# ctr_brd.net
KiCad netlist of a schematic drawn in EAGLE
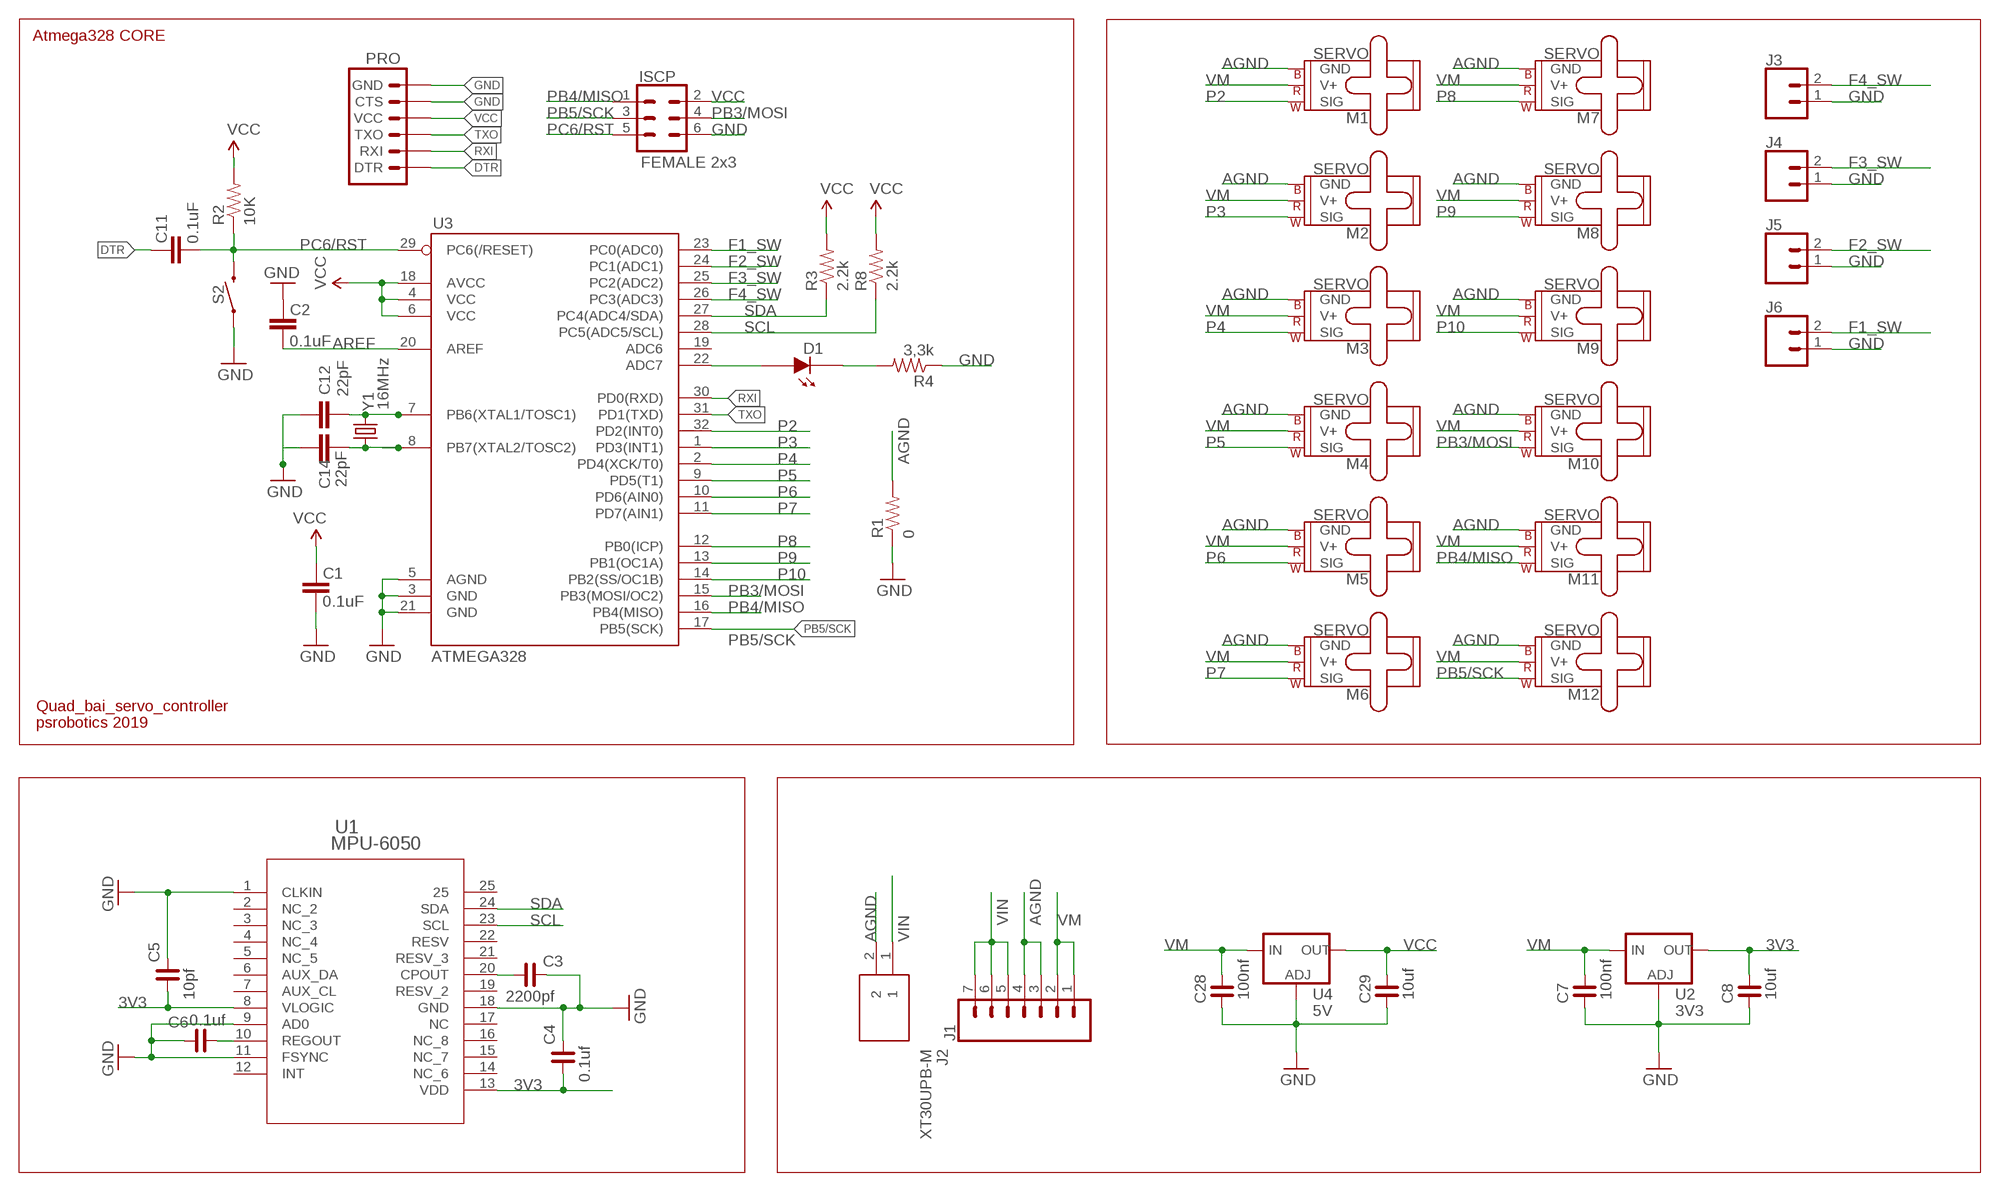
[diagram p0: schematic, sheet 1]

(export (version "E")
  (design (tool "Eeschema 10.0.6"))
  (components
    (comp (ref "C1")
      (value "0.1uF")
      (footprint "eagle-import:0603-CAP")
      (libsource (lib "eagle-import") (part "CAP0603-CAP"))
    )
    (comp (ref "C2")
      (value "0.1uF")
      (footprint "eagle-import:0603-CAP")
      (libsource (lib "eagle-import") (part "CAP0603-CAP"))
    )
    (comp (ref "C3")
      (value "2200pf")
      (footprint "eagle-import:C0603")
      (libsource (lib "eagle-import") (part "C_0603"))
    )
    (comp (ref "C4")
      (value "0.1uf")
      (footprint "eagle-import:C0603")
      (libsource (lib "eagle-import") (part "C_0603"))
    )
    (comp (ref "C5")
      (value "10pf")
      (footprint "eagle-import:C0603")
      (libsource (lib "eagle-import") (part "C_0603"))
    )
    (comp (ref "C6")
      (value "0.1uf")
      (footprint "eagle-import:C0603")
      (libsource (lib "eagle-import") (part "C_0603"))
    )
    (comp (ref "C7")
      (value "100nf")
      (footprint "eagle-import:C0603")
      (libsource (lib "eagle-import") (part "C_0603"))
    )
    (comp (ref "C8")
      (value "10uf")
      (footprint "eagle-import:C0603")
      (libsource (lib "eagle-import") (part "C_0603"))
    )
    (comp (ref "C11")
      (value "0.1uF")
      (footprint "eagle-import:0603-CAP")
      (libsource (lib "eagle-import") (part "CAP0603-CAP"))
    )
    (comp (ref "C12")
      (value "22pF")
      (footprint "eagle-import:0603")
      (libsource (lib "eagle-import") (part "22PF-0603-50V-5%"))
    )
    (comp (ref "C14")
      (value "22pF")
      (footprint "eagle-import:0603")
      (libsource (lib "eagle-import") (part "22PF-0603-50V-5%"))
    )
    (comp (ref "C28")
      (value "100nf")
      (footprint "eagle-import:C0603")
      (libsource (lib "eagle-import") (part "C_0603"))
    )
    (comp (ref "C29")
      (value "10uf")
      (footprint "eagle-import:C0603")
      (libsource (lib "eagle-import") (part "C_0603"))
    )
    (comp (ref "D1")
      (value "LEDB")
      (footprint "eagle-import:0603P")
      (libsource (lib "eagle-import") (part "LEDB"))
    )
    (comp (ref "ISCP")
      (value "FEMALE 2x3")
      (footprint "eagle-import:2X3")
      (libsource (lib "eagle-import") (part "CONN_03X2FEMALE"))
    )
    (comp (ref "J1")
      (value "CONN_07LONGPADS")
      (footprint "eagle-import:1X07_LONGPADS")
      (libsource (lib "eagle-import") (part "CONN_07LONGPADS"))
    )
    (comp (ref "J2")
      (value "XT30UPB-M")
      (footprint "eagle-import:SHDR2W160P0X500_1X2_1020X520X1")
      (libsource (lib "eagle-import") (part "XT30UPB-M"))
    )
    (comp (ref "J3")
      (value "CONN_02LOCK")
      (footprint "eagle-import:1X02_LOCK")
      (libsource (lib "eagle-import") (part "CONN_02LOCK"))
    )
    (comp (ref "J4")
      (value "CONN_02LOCK")
      (footprint "eagle-import:1X02_LOCK")
      (libsource (lib "eagle-import") (part "CONN_02LOCK"))
    )
    (comp (ref "J5")
      (value "CONN_02LOCK")
      (footprint "eagle-import:1X02_LOCK")
      (libsource (lib "eagle-import") (part "CONN_02LOCK"))
    )
    (comp (ref "J6")
      (value "CONN_02LOCK")
      (footprint "eagle-import:1X02_LOCK")
      (libsource (lib "eagle-import") (part "CONN_02LOCK"))
    )
    (comp (ref "M1")
      (value "SERVO")
      (footprint "eagle-import:1X03")
      (libsource (lib "eagle-import") (part "SERVO"))
    )
    (comp (ref "M2")
      (value "SERVO")
      (footprint "eagle-import:1X03")
      (libsource (lib "eagle-import") (part "SERVO"))
    )
    (comp (ref "M3")
      (value "SERVO")
      (footprint "eagle-import:1X03")
      (libsource (lib "eagle-import") (part "SERVO"))
    )
    (comp (ref "M4")
      (value "SERVO")
      (footprint "eagle-import:1X03")
      (libsource (lib "eagle-import") (part "SERVO"))
    )
    (comp (ref "M5")
      (value "SERVO")
      (footprint "eagle-import:1X03")
      (libsource (lib "eagle-import") (part "SERVO"))
    )
    (comp (ref "M6")
      (value "SERVO")
      (footprint "eagle-import:1X03")
      (libsource (lib "eagle-import") (part "SERVO"))
    )
    (comp (ref "M7")
      (value "SERVO")
      (footprint "eagle-import:1X03")
      (libsource (lib "eagle-import") (part "SERVO"))
    )
    (comp (ref "M8")
      (value "SERVO")
      (footprint "eagle-import:1X03")
      (libsource (lib "eagle-import") (part "SERVO"))
    )
    (comp (ref "M9")
      (value "SERVO")
      (footprint "eagle-import:1X03")
      (libsource (lib "eagle-import") (part "SERVO"))
    )
    (comp (ref "M10")
      (value "SERVO")
      (footprint "eagle-import:1X03")
      (libsource (lib "eagle-import") (part "SERVO"))
    )
    (comp (ref "M11")
      (value "SERVO")
      (footprint "eagle-import:1X03")
      (libsource (lib "eagle-import") (part "SERVO"))
    )
    (comp (ref "M12")
      (value "SERVO")
      (footprint "eagle-import:1X03")
      (libsource (lib "eagle-import") (part "SERVO"))
    )
    (comp (ref "PRO")
      (value "FTDI Basic")
      (footprint "eagle-import:1X06")
      (libsource (lib "eagle-import") (part "ARDUINO_SERIAL_PROGRAMPTH"))
    )
    (comp (ref "R1")
      (value "0")
      (footprint "eagle-import:0603-RES")
      (libsource (lib "eagle-import") (part "RESISTOR0603-RES"))
    )
    (comp (ref "R2")
      (value "10K")
      (footprint "eagle-import:0603-RES")
      (libsource (lib "eagle-import") (part "RESISTOR0603-RES"))
    )
    (comp (ref "R3")
      (value "2.2k")
      (footprint "eagle-import:0603-RES")
      (libsource (lib "eagle-import") (part "RESISTOR0603-RES"))
    )
    (comp (ref "R4")
      (value "3,3k")
      (footprint "eagle-import:0603-RES")
      (libsource (lib "eagle-import") (part "RESISTOR0603-RES"))
    )
    (comp (ref "R8")
      (value "2.2k")
      (footprint "eagle-import:0603-RES")
      (libsource (lib "eagle-import") (part "RESISTOR0603-RES"))
    )
    (comp (ref "S2")
      (value "MOMENTARY-SWITCH-SPST-SMD-6.0X3.5MM")
      (footprint "eagle-import:TACTILE_SWITCH_SMD_6.0X3.5MM")
      (libsource (lib "eagle-import") (part "MOMENTARY-SWITCH-SPST-SMD-6.0X3.5MM"))
    )
    (comp (ref "U1")
      (value "MPU-6050")
      (footprint "eagle-import:QFN24_4X4X0P9_IVS")
      (fields (field (name "COPYRIGHT") "Copyright (C) 2018 Accelerated Designs. All rights reserved"))
      (libsource (lib "eagle-import") (part "MPU-6050"))
    )
    (comp (ref "U2")
      (value "3V3")
      (footprint "eagle-import:SOT223")
      (libsource (lib "eagle-import") (part "V_REG_LM1117SOT223"))
    )
    (comp (ref "U3")
      (value "ATMEGA328")
      (footprint "eagle-import:TQFP32-08")
      (libsource (lib "eagle-import") (part "ATMEGA168"))
    )
    (comp (ref "U4")
      (value "5V")
      (footprint "eagle-import:SOT223")
      (libsource (lib "eagle-import") (part "V_REG_LM1117SOT223"))
    )
    (comp (ref "Y1")
      (value "16MHz")
      (footprint "eagle-import:CRYSTAL-SMD-5X3.2-4PAD")
      (libsource (lib "eagle-import") (part "CRYSTAL-16MHZSMD-5X3.2"))
    )
  )
  (nets
    (net (code "1") (name "/3V3") (class "Default")
      (node (ref "C4") (pin "1") (pinfunction "1_1") (pintype "passive"))
      (node (ref "C5") (pin "1") (pinfunction "1_1") (pintype "passive"))
      (node (ref "C8") (pin "2") (pinfunction "2_2") (pintype "passive"))
      (node (ref "U1") (pin "13") (pinfunction "VDD_13") (pintype "power_in"))
      (node (ref "U1") (pin "8") (pinfunction "VLOGIC_8") (pintype "power_in"))
      (node (ref "U2") (pin "2") (pinfunction "OUT_2") (pintype "output"))
      (node (ref "U2") (pin "4") (pinfunction "OUT_4") (pintype "output"))
    )
    (net (code "2") (name "/AGND") (class "Default")
      (node (ref "J1") (pin "3") (pinfunction "3_3") (pintype "passive"))
      (node (ref "J1") (pin "4") (pinfunction "4_4") (pintype "passive"))
      (node (ref "J2") (pin "2") (pinfunction "2_2") (pintype "bidirectional"))
      (node (ref "M1") (pin "3") (pinfunction "GND_3") (pintype "bidirectional"))
      (node (ref "M10") (pin "3") (pinfunction "GND_3") (pintype "bidirectional"))
      (node (ref "M11") (pin "3") (pinfunction "GND_3") (pintype "bidirectional"))
      (node (ref "M12") (pin "3") (pinfunction "GND_3") (pintype "bidirectional"))
      (node (ref "M2") (pin "3") (pinfunction "GND_3") (pintype "bidirectional"))
      (node (ref "M3") (pin "3") (pinfunction "GND_3") (pintype "bidirectional"))
      (node (ref "M4") (pin "3") (pinfunction "GND_3") (pintype "bidirectional"))
      (node (ref "M5") (pin "3") (pinfunction "GND_3") (pintype "bidirectional"))
      (node (ref "M6") (pin "3") (pinfunction "GND_3") (pintype "bidirectional"))
      (node (ref "M7") (pin "3") (pinfunction "GND_3") (pintype "bidirectional"))
      (node (ref "M8") (pin "3") (pinfunction "GND_3") (pintype "bidirectional"))
      (node (ref "M9") (pin "3") (pinfunction "GND_3") (pintype "bidirectional"))
      (node (ref "R1") (pin "2") (pinfunction "2_2") (pintype "passive"))
    )
    (net (code "3") (name "/AREF") (class "Default")
      (node (ref "C2") (pin "1") (pinfunction "1_1") (pintype "passive"))
      (node (ref "U3") (pin "20") (pinfunction "AREF_20") (pintype "bidirectional"))
    )
    (net (code "4") (name "/F1_SW") (class "Default")
      (node (ref "J6") (pin "2") (pinfunction "2_2") (pintype "passive"))
      (node (ref "U3") (pin "23") (pinfunction "PC0(ADC0)_23") (pintype "bidirectional"))
    )
    (net (code "5") (name "/F2_SW") (class "Default")
      (node (ref "J5") (pin "2") (pinfunction "2_2") (pintype "passive"))
      (node (ref "U3") (pin "24") (pinfunction "PC1(ADC1)_24") (pintype "bidirectional"))
    )
    (net (code "6") (name "/F3_SW") (class "Default")
      (node (ref "J4") (pin "2") (pinfunction "2_2") (pintype "passive"))
      (node (ref "U3") (pin "25") (pinfunction "PC2(ADC2)_25") (pintype "bidirectional"))
    )
    (net (code "7") (name "/F4_SW") (class "Default")
      (node (ref "J3") (pin "2") (pinfunction "2_2") (pintype "passive"))
      (node (ref "U3") (pin "26") (pinfunction "PC3(ADC3)_26") (pintype "bidirectional"))
    )
    (net (code "8") (name "/P2") (class "Default")
      (node (ref "M1") (pin "1") (pinfunction "SIG_1") (pintype "bidirectional"))
      (node (ref "U3") (pin "32") (pinfunction "PD2(INT0)_32") (pintype "bidirectional"))
    )
    (net (code "9") (name "/P3") (class "Default")
      (node (ref "M2") (pin "1") (pinfunction "SIG_1") (pintype "bidirectional"))
      (node (ref "U3") (pin "1") (pinfunction "PD3(INT1)_1") (pintype "bidirectional"))
    )
    (net (code "10") (name "/P4") (class "Default")
      (node (ref "M3") (pin "1") (pinfunction "SIG_1") (pintype "bidirectional"))
      (node (ref "U3") (pin "2") (pinfunction "PD4(XCK/T0)_2") (pintype "bidirectional"))
    )
    (net (code "11") (name "/P5") (class "Default")
      (node (ref "M4") (pin "1") (pinfunction "SIG_1") (pintype "bidirectional"))
      (node (ref "U3") (pin "9") (pinfunction "PD5(T1)_9") (pintype "bidirectional"))
    )
    (net (code "12") (name "/P6") (class "Default")
      (node (ref "M5") (pin "1") (pinfunction "SIG_1") (pintype "bidirectional"))
      (node (ref "U3") (pin "10") (pinfunction "PD6(AIN0)_10") (pintype "bidirectional"))
    )
    (net (code "13") (name "/P7") (class "Default")
      (node (ref "M6") (pin "1") (pinfunction "SIG_1") (pintype "bidirectional"))
      (node (ref "U3") (pin "11") (pinfunction "PD7(AIN1)_11") (pintype "bidirectional"))
    )
    (net (code "14") (name "/P8") (class "Default")
      (node (ref "M7") (pin "1") (pinfunction "SIG_1") (pintype "bidirectional"))
      (node (ref "U3") (pin "12") (pinfunction "PB0(ICP)_12") (pintype "bidirectional"))
    )
    (net (code "15") (name "/P9") (class "Default")
      (node (ref "M8") (pin "1") (pinfunction "SIG_1") (pintype "bidirectional"))
      (node (ref "U3") (pin "13") (pinfunction "PB1(OC1A)_13") (pintype "bidirectional"))
    )
    (net (code "16") (name "/P10") (class "Default")
      (node (ref "M9") (pin "1") (pinfunction "SIG_1") (pintype "bidirectional"))
      (node (ref "U3") (pin "14") (pinfunction "PB2(SS/OC1B)_14") (pintype "bidirectional"))
    )
    (net (code "17") (name "/PB3{slash}MOSI") (class "Default")
      (node (ref "ISCP") (pin "4") (pinfunction "4_4") (pintype "bidirectional"))
      (node (ref "M10") (pin "1") (pinfunction "SIG_1") (pintype "bidirectional"))
      (node (ref "U3") (pin "15") (pinfunction "PB3(MOSI/OC2)_15") (pintype "bidirectional"))
    )
    (net (code "18") (name "/PB4{slash}MISO") (class "Default")
      (node (ref "ISCP") (pin "1") (pinfunction "1_1") (pintype "bidirectional"))
      (node (ref "M11") (pin "1") (pinfunction "SIG_1") (pintype "bidirectional"))
      (node (ref "U3") (pin "16") (pinfunction "PB4(MISO)_16") (pintype "bidirectional"))
    )
    (net (code "19") (name "/PC6{slash}RST") (class "Default")
      (node (ref "C11") (pin "1") (pinfunction "1_1") (pintype "passive"))
      (node (ref "ISCP") (pin "5") (pinfunction "5_5") (pintype "bidirectional"))
      (node (ref "R2") (pin "1") (pinfunction "1_1") (pintype "passive"))
      (node (ref "S2") (pin "2") (pinfunction "2_2") (pintype "passive"))
      (node (ref "U3") (pin "29") (pinfunction "PC6(/RESET)_29") (pintype "bidirectional"))
    )
    (net (code "20") (name "/SCL") (class "Default")
      (node (ref "R8") (pin "1") (pinfunction "1_1") (pintype "passive"))
      (node (ref "U1") (pin "23") (pinfunction "SCL_23") (pintype "passive"))
      (node (ref "U3") (pin "28") (pinfunction "PC5(ADC5/SCL)_28") (pintype "bidirectional"))
    )
    (net (code "21") (name "/SDA") (class "Default")
      (node (ref "R3") (pin "1") (pinfunction "1_1") (pintype "passive"))
      (node (ref "U1") (pin "24") (pinfunction "SDA_24") (pintype "passive"))
      (node (ref "U3") (pin "27") (pinfunction "PC4(ADC4/SDA)_27") (pintype "bidirectional"))
    )
    (net (code "22") (name "/VIN") (class "Default")
      (node (ref "J1") (pin "5") (pinfunction "5_5") (pintype "passive"))
      (node (ref "J1") (pin "6") (pinfunction "6_6") (pintype "passive"))
      (node (ref "J1") (pin "7") (pinfunction "7_7") (pintype "passive"))
      (node (ref "J2") (pin "1") (pinfunction "1_1") (pintype "bidirectional"))
    )
    (net (code "23") (name "/VM") (class "Default")
      (node (ref "C28") (pin "2") (pinfunction "2_2") (pintype "passive"))
      (node (ref "C7") (pin "2") (pinfunction "2_2") (pintype "passive"))
      (node (ref "J1") (pin "1") (pinfunction "1_1") (pintype "passive"))
      (node (ref "J1") (pin "2") (pinfunction "2_2") (pintype "passive"))
      (node (ref "M1") (pin "2") (pinfunction "V+_2") (pintype "bidirectional"))
      (node (ref "M10") (pin "2") (pinfunction "V+_2") (pintype "bidirectional"))
      (node (ref "M11") (pin "2") (pinfunction "V+_2") (pintype "bidirectional"))
      (node (ref "M12") (pin "2") (pinfunction "V+_2") (pintype "bidirectional"))
      (node (ref "M2") (pin "2") (pinfunction "V+_2") (pintype "bidirectional"))
      (node (ref "M3") (pin "2") (pinfunction "V+_2") (pintype "bidirectional"))
      (node (ref "M4") (pin "2") (pinfunction "V+_2") (pintype "bidirectional"))
      (node (ref "M5") (pin "2") (pinfunction "V+_2") (pintype "bidirectional"))
      (node (ref "M6") (pin "2") (pinfunction "V+_2") (pintype "bidirectional"))
      (node (ref "M7") (pin "2") (pinfunction "V+_2") (pintype "bidirectional"))
      (node (ref "M8") (pin "2") (pinfunction "V+_2") (pintype "bidirectional"))
      (node (ref "M9") (pin "2") (pinfunction "V+_2") (pintype "bidirectional"))
      (node (ref "U2") (pin "3") (pinfunction "IN_3") (pintype "input"))
      (node (ref "U4") (pin "3") (pinfunction "IN_3") (pintype "input"))
    )
    (net (code "24") (name "DTR") (class "Default")
      (node (ref "C11") (pin "2") (pinfunction "2_2") (pintype "passive"))
      (node (ref "PRO") (pin "1") (pinfunction "DTR_1") (pintype "passive"))
    )
    (net (code "25") (name "GND") (class "Default")
      (node (ref "C1") (pin "1") (pinfunction "1_1") (pintype "passive"))
      (node (ref "C12") (pin "1") (pinfunction "1_1") (pintype "passive"))
      (node (ref "C14") (pin "1") (pinfunction "1_1") (pintype "passive"))
      (node (ref "C2") (pin "2") (pinfunction "2_2") (pintype "passive"))
      (node (ref "C28") (pin "1") (pinfunction "1_1") (pintype "passive"))
      (node (ref "C29") (pin "1") (pinfunction "1_1") (pintype "passive"))
      (node (ref "C3") (pin "2") (pinfunction "2_2") (pintype "passive"))
      (node (ref "C4") (pin "2") (pinfunction "2_2") (pintype "passive"))
      (node (ref "C5") (pin "2") (pinfunction "2_2") (pintype "passive"))
      (node (ref "C6") (pin "2") (pinfunction "2_2") (pintype "passive"))
      (node (ref "C7") (pin "1") (pinfunction "1_1") (pintype "passive"))
      (node (ref "C8") (pin "1") (pinfunction "1_1") (pintype "passive"))
      (node (ref "ISCP") (pin "6") (pinfunction "6_6") (pintype "bidirectional"))
      (node (ref "J3") (pin "1") (pinfunction "1_1") (pintype "passive"))
      (node (ref "J4") (pin "1") (pinfunction "1_1") (pintype "passive"))
      (node (ref "J5") (pin "1") (pinfunction "1_1") (pintype "passive"))
      (node (ref "J6") (pin "1") (pinfunction "1_1") (pintype "passive"))
      (node (ref "PRO") (pin "5") (pinfunction "CTS_5") (pintype "passive"))
      (node (ref "PRO") (pin "6") (pinfunction "GND_6") (pintype "passive"))
      (node (ref "R1") (pin "1") (pinfunction "1_1") (pintype "passive"))
      (node (ref "R4") (pin "1") (pinfunction "1_1") (pintype "passive"))
      (node (ref "S2") (pin "1") (pinfunction "1_1") (pintype "passive"))
      (node (ref "U1") (pin "1") (pinfunction "CLKIN_1") (pintype "input"))
      (node (ref "U1") (pin "11") (pinfunction "FSYNC_11") (pintype "input"))
      (node (ref "U1") (pin "18") (pinfunction "GND_18") (pintype "passive"))
      (node (ref "U1") (pin "9") (pinfunction "AD0_9") (pintype "bidirectional"))
      (node (ref "U2") (pin "1") (pinfunction "ADJ_1") (pintype "input"))
      (node (ref "U3") (pin "21") (pinfunction "GND_21") (pintype "bidirectional"))
      (node (ref "U3") (pin "3") (pinfunction "GND_3") (pintype "bidirectional"))
      (node (ref "U3") (pin "5") (pinfunction "AGND_5") (pintype "bidirectional"))
      (node (ref "U4") (pin "1") (pinfunction "ADJ_1") (pintype "input"))
    )
    (net (code "26") (name "Net-(D1-D_IN)") (class "Default")
      (node (ref "D1") (pin "1") (pinfunction "D_IN_1") (pintype "passive"))
      (node (ref "U3") (pin "22") (pinfunction "ADC7_22") (pintype "bidirectional"))
    )
    (net (code "27") (name "Net-(D1-D_OUT)") (class "Default")
      (node (ref "D1") (pin "2") (pinfunction "D_OUT_2") (pintype "passive"))
      (node (ref "R4") (pin "2") (pinfunction "2_2") (pintype "passive"))
    )
    (net (code "28") (name "Net-(U1-CPOUT)") (class "Default")
      (node (ref "C3") (pin "1") (pinfunction "1_1") (pintype "passive"))
      (node (ref "U1") (pin "20") (pinfunction "CPOUT_20") (pintype "passive"))
    )
    (net (code "29") (name "Net-(U1-REGOUT)") (class "Default")
      (node (ref "C6") (pin "1") (pinfunction "1_1") (pintype "passive"))
      (node (ref "U1") (pin "10") (pinfunction "REGOUT_10") (pintype "passive"))
    )
    (net (code "30") (name "Net-(U3-PB6(XTAL1{slash}TOSC1))") (class "Default")
      (node (ref "C12") (pin "2") (pinfunction "2_2") (pintype "passive"))
      (node (ref "U3") (pin "7") (pinfunction "PB6(XTAL1/TOSC1)_7") (pintype "bidirectional"))
      (node (ref "Y1") (pin "3") (pinfunction "2_3") (pintype "passive"))
    )
    (net (code "31") (name "Net-(U3-PB7(XTAL2{slash}TOSC2))") (class "Default")
      (node (ref "C14") (pin "2") (pinfunction "2_2") (pintype "passive"))
      (node (ref "U3") (pin "8") (pinfunction "PB7(XTAL2/TOSC2)_8") (pintype "bidirectional"))
      (node (ref "Y1") (pin "1") (pinfunction "1_1") (pintype "passive"))
    )
    (net (code "32") (name "PB5{slash}SCK") (class "Default")
      (node (ref "ISCP") (pin "3") (pinfunction "3_3") (pintype "bidirectional"))
      (node (ref "M12") (pin "1") (pinfunction "SIG_1") (pintype "bidirectional"))
      (node (ref "U3") (pin "17") (pinfunction "PB5(SCK)_17") (pintype "bidirectional"))
    )
    (net (code "33") (name "RXI") (class "Default")
      (node (ref "PRO") (pin "2") (pinfunction "RXI_2") (pintype "passive"))
      (node (ref "U3") (pin "30") (pinfunction "PD0(RXD)_30") (pintype "bidirectional"))
    )
    (net (code "34") (name "TXO") (class "Default")
      (node (ref "PRO") (pin "3") (pinfunction "TXO_3") (pintype "passive"))
      (node (ref "U3") (pin "31") (pinfunction "PD1(TXD)_31") (pintype "bidirectional"))
    )
    (net (code "35") (name "VCC") (class "Default")
      (node (ref "C1") (pin "2") (pinfunction "2_2") (pintype "passive"))
      (node (ref "C29") (pin "2") (pinfunction "2_2") (pintype "passive"))
      (node (ref "ISCP") (pin "2") (pinfunction "2_2") (pintype "bidirectional"))
      (node (ref "PRO") (pin "4") (pinfunction "VCC_4") (pintype "passive"))
      (node (ref "R2") (pin "2") (pinfunction "2_2") (pintype "passive"))
      (node (ref "R3") (pin "2") (pinfunction "2_2") (pintype "passive"))
      (node (ref "R8") (pin "2") (pinfunction "2_2") (pintype "passive"))
      (node (ref "U3") (pin "18") (pinfunction "AVCC_18") (pintype "bidirectional"))
      (node (ref "U3") (pin "4") (pinfunction "VCC_4") (pintype "bidirectional"))
      (node (ref "U3") (pin "6") (pinfunction "VCC_6") (pintype "bidirectional"))
      (node (ref "U4") (pin "2") (pinfunction "OUT_2") (pintype "output"))
      (node (ref "U4") (pin "4") (pinfunction "OUT_4") (pintype "output"))
    )
    (net (code "36") (name "unconnected-(U1-AUX_CL-Pad7)") (class "Default")
      (node (ref "U1") (pin "7") (pinfunction "AUX_CL_7") (pintype "passive"))
    )
    (net (code "37") (name "unconnected-(U1-AUX_DA-Pad6)") (class "Default")
      (node (ref "U1") (pin "6") (pinfunction "AUX_DA_6") (pintype "passive"))
    )
    (net (code "38") (name "unconnected-(U1-INT-Pad12)") (class "Default")
      (node (ref "U1") (pin "12") (pinfunction "INT_12") (pintype "output"))
    )
    (net (code "39") (name "unconnected-(U1-NC-Pad17)") (class "Default")
      (node (ref "U1") (pin "17") (pinfunction "NC_17") (pintype "no_connect"))
    )
    (net (code "40") (name "unconnected-(U1-NC_2-Pad2)") (class "Default")
      (node (ref "U1") (pin "2") (pinfunction "NC_2_2") (pintype "no_connect"))
    )
    (net (code "41") (name "unconnected-(U1-NC_3-Pad3)") (class "Default")
      (node (ref "U1") (pin "3") (pinfunction "NC_3_3") (pintype "no_connect"))
    )
    (net (code "42") (name "unconnected-(U1-NC_4-Pad4)") (class "Default")
      (node (ref "U1") (pin "4") (pinfunction "NC_4_4") (pintype "no_connect"))
    )
    (net (code "43") (name "unconnected-(U1-NC_5-Pad5)") (class "Default")
      (node (ref "U1") (pin "5") (pinfunction "NC_5_5") (pintype "no_connect"))
    )
    (net (code "44") (name "unconnected-(U1-NC_6-Pad14)") (class "Default")
      (node (ref "U1") (pin "14") (pinfunction "NC_6_14") (pintype "no_connect"))
    )
    (net (code "45") (name "unconnected-(U1-NC_7-Pad15)") (class "Default")
      (node (ref "U1") (pin "15") (pinfunction "NC_7_15") (pintype "no_connect"))
    )
    (net (code "46") (name "unconnected-(U1-NC_8-Pad16)") (class "Default")
      (node (ref "U1") (pin "16") (pinfunction "NC_8_16") (pintype "no_connect"))
    )
    (net (code "47") (name "unconnected-(U1-Pad25)") (class "Default")
      (node (ref "U1") (pin "25") (pinfunction "25_25") (pintype "passive"))
    )
    (net (code "48") (name "unconnected-(U1-RESV-Pad22)") (class "Default")
      (node (ref "U1") (pin "22") (pinfunction "RESV_22") (pintype "no_connect"))
    )
    (net (code "49") (name "unconnected-(U1-RESV_2-Pad19)") (class "Default")
      (node (ref "U1") (pin "19") (pinfunction "RESV_2_19") (pintype "no_connect"))
    )
    (net (code "50") (name "unconnected-(U1-RESV_3-Pad21)") (class "Default")
      (node (ref "U1") (pin "21") (pinfunction "RESV_3_21") (pintype "no_connect"))
    )
    (net (code "51") (name "unconnected-(U3-ADC6-Pad19)") (class "Default")
      (node (ref "U3") (pin "19") (pinfunction "ADC6_19") (pintype "bidirectional"))
    )
  )
)
